# schematic.net
KiCad netlist of a schematic drawn in EAGLE
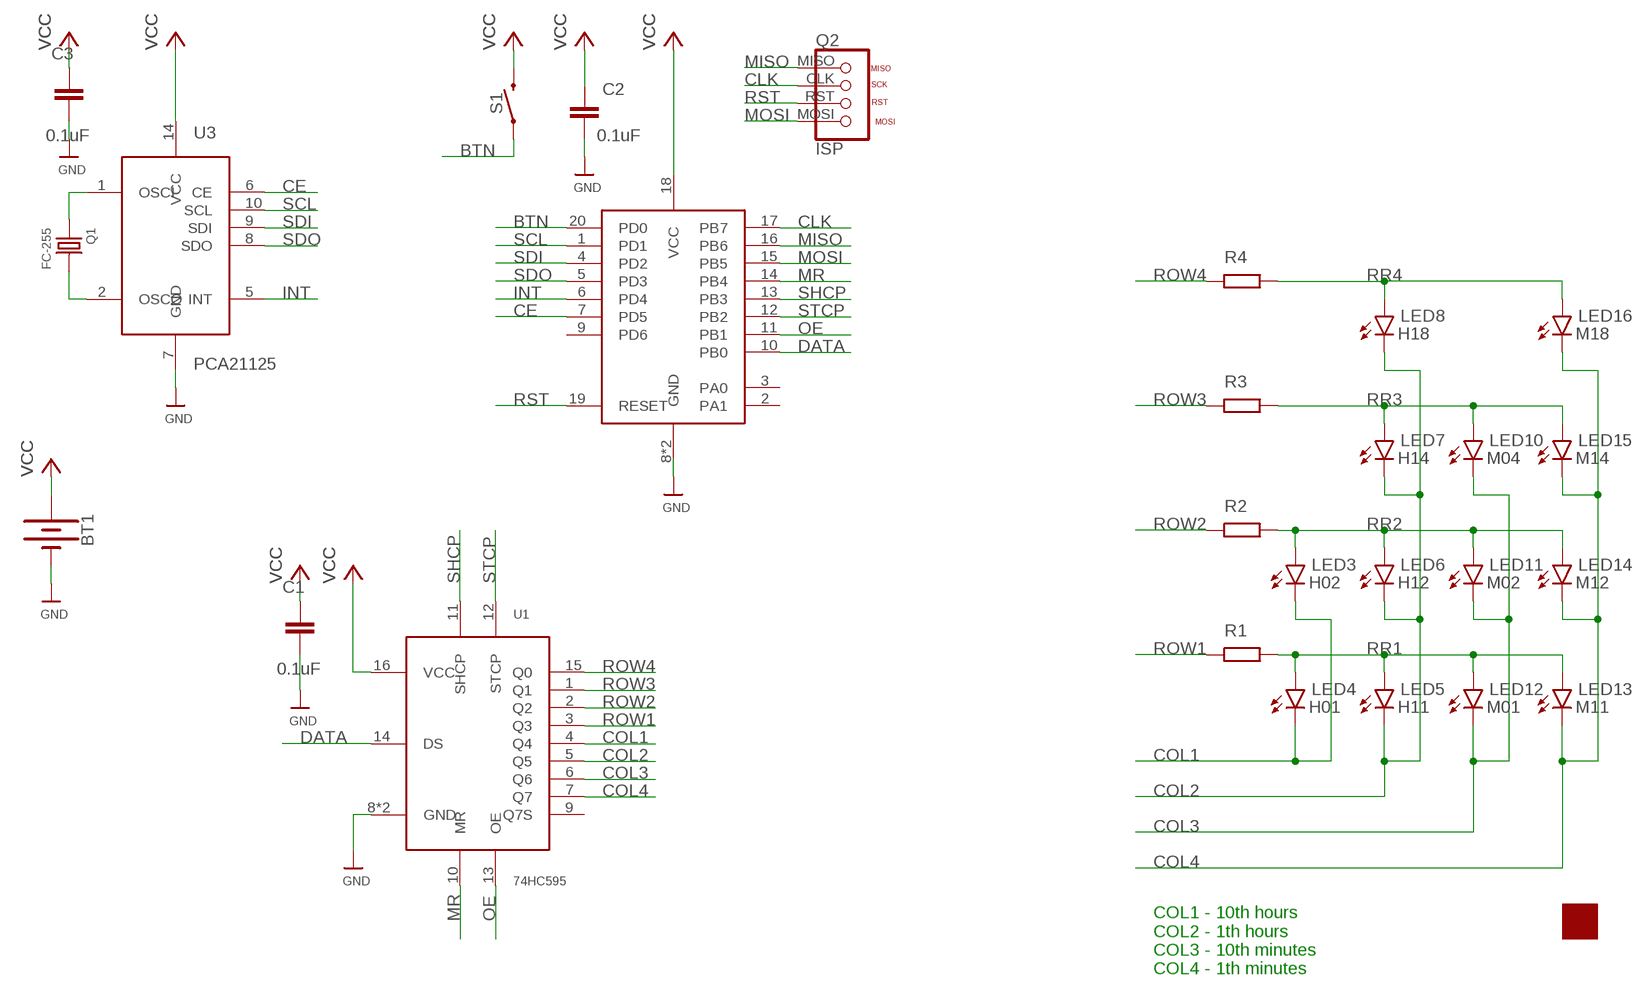
[diagram p0: schematic, sheet 1]

(export (version "E")
  (design (tool "Eeschema 10.0.6"))
  (components
    (comp (ref "BT1")
      (value "BATTERY-12MM_SMD")
      (footprint "eagle-import:BATTCON_12MM")
      (libsource (lib "eagle-import") (part "BATTERY-12MM_SMD"))
    )
    (comp (ref "C1")
      (value "0.1uF")
      (footprint "eagle-import:CAP_0402")
      (fields
        (field (name "DIGIKEY_PART_NUMBER") "311-2076-2-ND")
        (field (name "MANUFACTURER") "Yageo")
        (field (name "MPN") "CC0402CRNPO9BN1R0")
        (field (name "CREATED_BY") "PCBLayout.com")
      )
      (libsource (lib "eagle-import") (part "CC0402CRNPO9BN1R0"))
    )
    (comp (ref "C2")
      (value "0.1uF")
      (footprint "eagle-import:CAP_0402")
      (fields
        (field (name "DIGIKEY_PART_NUMBER") "311-2076-2-ND")
        (field (name "MANUFACTURER") "Yageo")
        (field (name "MPN") "CC0402CRNPO9BN1R0")
        (field (name "CREATED_BY") "PCBLayout.com")
      )
      (libsource (lib "eagle-import") (part "CC0402CRNPO9BN1R0"))
    )
    (comp (ref "C3")
      (value "0.1uF")
      (footprint "eagle-import:CAP_0402")
      (fields
        (field (name "DIGIKEY_PART_NUMBER") "311-2076-2-ND")
        (field (name "MANUFACTURER") "Yageo")
        (field (name "MPN") "CC0402CRNPO9BN1R0")
        (field (name "CREATED_BY") "PCBLayout.com")
      )
      (libsource (lib "eagle-import") (part "CC0402CRNPO9BN1R0"))
    )
    (comp (ref "IMG1")
      (value "IMAGE")
      (footprint "eagle-import:IMG6")
      (libsource (lib "eagle-import") (part "IMAGE"))
    )
    (comp (ref "LED3")
      (value "H02")
      (footprint "eagle-import:LG-T67K")
      (libsource (lib "eagle-import") (part "LG-T67K"))
    )
    (comp (ref "LED4")
      (value "H01")
      (footprint "eagle-import:LG-T67K")
      (libsource (lib "eagle-import") (part "LG-T67K"))
    )
    (comp (ref "LED5")
      (value "H11")
      (footprint "eagle-import:LG-T67K")
      (libsource (lib "eagle-import") (part "LG-T67K"))
    )
    (comp (ref "LED6")
      (value "H12")
      (footprint "eagle-import:LG-T67K")
      (libsource (lib "eagle-import") (part "LG-T67K"))
    )
    (comp (ref "LED7")
      (value "H14")
      (footprint "eagle-import:LG-T67K")
      (libsource (lib "eagle-import") (part "LG-T67K"))
    )
    (comp (ref "LED8")
      (value "H18")
      (footprint "eagle-import:LG-T67K")
      (libsource (lib "eagle-import") (part "LG-T67K"))
    )
    (comp (ref "LED10")
      (value "M04")
      (footprint "eagle-import:LG-T67K")
      (libsource (lib "eagle-import") (part "LG-T67K"))
    )
    (comp (ref "LED11")
      (value "M02")
      (footprint "eagle-import:LG-T67K")
      (libsource (lib "eagle-import") (part "LG-T67K"))
    )
    (comp (ref "LED12")
      (value "M01")
      (footprint "eagle-import:LG-T67K")
      (libsource (lib "eagle-import") (part "LG-T67K"))
    )
    (comp (ref "LED13")
      (value "M11")
      (footprint "eagle-import:LG-T67K")
      (libsource (lib "eagle-import") (part "LG-T67K"))
    )
    (comp (ref "LED14")
      (value "M12")
      (footprint "eagle-import:LG-T67K")
      (libsource (lib "eagle-import") (part "LG-T67K"))
    )
    (comp (ref "LED15")
      (value "M14")
      (footprint "eagle-import:LG-T67K")
      (libsource (lib "eagle-import") (part "LG-T67K"))
    )
    (comp (ref "LED16")
      (value "M18")
      (footprint "eagle-import:LG-T67K")
      (libsource (lib "eagle-import") (part "LG-T67K"))
    )
    (comp (ref "Q1")
      (value "FC-255")
      (footprint "eagle-import:FC-255")
      (libsource (lib "eagle-import") (part "FC-255"))
    )
    (comp (ref "Q2")
      (value "ISP")
      (footprint "eagle-import:ISP")
      (libsource (lib "eagle-import") (part "ISP"))
    )
    (comp (ref "R1")
      (value "R_CHIP-0402(1005-METRIC)")
      (footprint "eagle-import:RESC1005X40")
      (libsource (lib "eagle-import") (part "RCHIP-0402(1005-METRIC)_"))
    )
    (comp (ref "R2")
      (value "R_CHIP-0402(1005-METRIC)")
      (footprint "eagle-import:RESC1005X40")
      (libsource (lib "eagle-import") (part "RCHIP-0402(1005-METRIC)_"))
    )
    (comp (ref "R3")
      (value "R_CHIP-0402(1005-METRIC)")
      (footprint "eagle-import:RESC1005X40")
      (libsource (lib "eagle-import") (part "RCHIP-0402(1005-METRIC)_"))
    )
    (comp (ref "R4")
      (value "R_CHIP-0402(1005-METRIC)")
      (footprint "eagle-import:RESC1005X40")
      (libsource (lib "eagle-import") (part "RCHIP-0402(1005-METRIC)_"))
    )
    (comp (ref "S1")
      (value "MOMENTARY-SWITCH-SPST-SMD-6.2MM-TALL")
      (footprint "eagle-import:TACTILE_SWITCH_SMD_6.2MM_TALL")
      (libsource (lib "eagle-import") (part "MOMENTARY-SWITCH-SPST-SMD-6.2MM-TALL"))
    )
    (comp (ref "U1")
      (value "74HC595")
      (footprint "eagle-import:DHVQFN16")
      (libsource (lib "eagle-import") (part "74HC595"))
    )
    (comp (ref "U2")
      (value "ATTINY2313")
      (footprint "eagle-import:MLF20-4X4")
      (libsource (lib "eagle-import") (part "ATTINY2313AMLF20-4X4"))
    )
    (comp (ref "U3")
      (value "PCA21125")
      (footprint "eagle-import:TSSOP14")
      (libsource (lib "eagle-import") (part "PCA21125"))
    )
  )
  (nets
    (net (code "1") (name "/BTN") (class "Default")
      (node (ref "S1") (pin "A2") (pinfunction "1_A2") (pintype "passive"))
      (node (ref "U2") (pin "20") (pinfunction "PD0_20") (pintype "bidirectional"))
    )
    (net (code "2") (name "/CE") (class "Default")
      (node (ref "U2") (pin "7") (pinfunction "PD5_7") (pintype "bidirectional"))
      (node (ref "U3") (pin "6") (pinfunction "CE_6") (pintype "bidirectional"))
    )
    (net (code "3") (name "/CLK") (class "Default")
      (node (ref "Q2") (pin "CLK") (pinfunction "SCK_CLK") (pintype "passive"))
      (node (ref "U2") (pin "17") (pinfunction "PB7_17") (pintype "bidirectional"))
    )
    (net (code "4") (name "/COL1") (class "Default")
      (node (ref "LED3") (pin "P$2") (pinfunction "C_P$2") (pintype "passive"))
      (node (ref "LED4") (pin "P$2") (pinfunction "C_P$2") (pintype "passive"))
      (node (ref "U1") (pin "4") (pinfunction "Q4_4") (pintype "bidirectional"))
    )
    (net (code "5") (name "/COL2") (class "Default")
      (node (ref "LED5") (pin "P$2") (pinfunction "C_P$2") (pintype "passive"))
      (node (ref "LED6") (pin "P$2") (pinfunction "C_P$2") (pintype "passive"))
      (node (ref "LED7") (pin "P$2") (pinfunction "C_P$2") (pintype "passive"))
      (node (ref "LED8") (pin "P$2") (pinfunction "C_P$2") (pintype "passive"))
      (node (ref "U1") (pin "5") (pinfunction "Q5_5") (pintype "bidirectional"))
    )
    (net (code "6") (name "/COL3") (class "Default")
      (node (ref "LED10") (pin "P$2") (pinfunction "C_P$2") (pintype "passive"))
      (node (ref "LED11") (pin "P$2") (pinfunction "C_P$2") (pintype "passive"))
      (node (ref "LED12") (pin "P$2") (pinfunction "C_P$2") (pintype "passive"))
      (node (ref "U1") (pin "6") (pinfunction "Q6_6") (pintype "bidirectional"))
    )
    (net (code "7") (name "/COL4") (class "Default")
      (node (ref "LED13") (pin "P$2") (pinfunction "C_P$2") (pintype "passive"))
      (node (ref "LED14") (pin "P$2") (pinfunction "C_P$2") (pintype "passive"))
      (node (ref "LED15") (pin "P$2") (pinfunction "C_P$2") (pintype "passive"))
      (node (ref "LED16") (pin "P$2") (pinfunction "C_P$2") (pintype "passive"))
      (node (ref "U1") (pin "7") (pinfunction "Q7_7") (pintype "bidirectional"))
    )
    (net (code "8") (name "/DATA") (class "Default")
      (node (ref "U1") (pin "14") (pinfunction "DS_14") (pintype "bidirectional"))
      (node (ref "U2") (pin "10") (pinfunction "PB0_10") (pintype "bidirectional"))
    )
    (net (code "9") (name "/INT") (class "Default")
      (node (ref "U2") (pin "6") (pinfunction "PD4_6") (pintype "bidirectional"))
      (node (ref "U3") (pin "5") (pinfunction "INT_5") (pintype "bidirectional"))
    )
    (net (code "10") (name "/MISO") (class "Default")
      (node (ref "Q2") (pin "MISO") (pinfunction "MISO_MISO") (pintype "passive"))
      (node (ref "U2") (pin "16") (pinfunction "PB6_16") (pintype "bidirectional"))
    )
    (net (code "11") (name "/MOSI") (class "Default")
      (node (ref "Q2") (pin "MOSI") (pinfunction "MOSI_MOSI") (pintype "passive"))
      (node (ref "U2") (pin "15") (pinfunction "PB5_15") (pintype "bidirectional"))
    )
    (net (code "12") (name "/MR") (class "Default")
      (node (ref "U1") (pin "10") (pinfunction "MR_10") (pintype "bidirectional"))
      (node (ref "U2") (pin "14") (pinfunction "PB4_14") (pintype "bidirectional"))
    )
    (net (code "13") (name "/OE") (class "Default")
      (node (ref "U1") (pin "13") (pinfunction "OE_13") (pintype "bidirectional"))
      (node (ref "U2") (pin "11") (pinfunction "PB1_11") (pintype "bidirectional"))
    )
    (net (code "14") (name "/ROW1") (class "Default")
      (node (ref "R1") (pin "1") (pinfunction "1_1") (pintype "passive"))
      (node (ref "U1") (pin "3") (pinfunction "Q3_3") (pintype "bidirectional"))
    )
    (net (code "15") (name "/ROW2") (class "Default")
      (node (ref "R2") (pin "1") (pinfunction "1_1") (pintype "passive"))
      (node (ref "U1") (pin "2") (pinfunction "Q2_2") (pintype "bidirectional"))
    )
    (net (code "16") (name "/ROW3") (class "Default")
      (node (ref "R3") (pin "1") (pinfunction "1_1") (pintype "passive"))
      (node (ref "U1") (pin "1") (pinfunction "Q1_1") (pintype "bidirectional"))
    )
    (net (code "17") (name "/ROW4") (class "Default")
      (node (ref "R4") (pin "1") (pinfunction "1_1") (pintype "passive"))
      (node (ref "U1") (pin "15") (pinfunction "Q0_15") (pintype "bidirectional"))
    )
    (net (code "18") (name "/RR1") (class "Default")
      (node (ref "LED12") (pin "P$1") (pinfunction "A_P$1") (pintype "passive"))
      (node (ref "LED13") (pin "P$1") (pinfunction "A_P$1") (pintype "passive"))
      (node (ref "LED4") (pin "P$1") (pinfunction "A_P$1") (pintype "passive"))
      (node (ref "LED5") (pin "P$1") (pinfunction "A_P$1") (pintype "passive"))
      (node (ref "R1") (pin "2") (pinfunction "2_2") (pintype "passive"))
    )
    (net (code "19") (name "/RR2") (class "Default")
      (node (ref "LED11") (pin "P$1") (pinfunction "A_P$1") (pintype "passive"))
      (node (ref "LED14") (pin "P$1") (pinfunction "A_P$1") (pintype "passive"))
      (node (ref "LED3") (pin "P$1") (pinfunction "A_P$1") (pintype "passive"))
      (node (ref "LED6") (pin "P$1") (pinfunction "A_P$1") (pintype "passive"))
      (node (ref "R2") (pin "2") (pinfunction "2_2") (pintype "passive"))
    )
    (net (code "20") (name "/RR3") (class "Default")
      (node (ref "LED10") (pin "P$1") (pinfunction "A_P$1") (pintype "passive"))
      (node (ref "LED15") (pin "P$1") (pinfunction "A_P$1") (pintype "passive"))
      (node (ref "LED7") (pin "P$1") (pinfunction "A_P$1") (pintype "passive"))
      (node (ref "R3") (pin "2") (pinfunction "2_2") (pintype "passive"))
    )
    (net (code "21") (name "/RR4") (class "Default")
      (node (ref "LED16") (pin "P$1") (pinfunction "A_P$1") (pintype "passive"))
      (node (ref "LED8") (pin "P$1") (pinfunction "A_P$1") (pintype "passive"))
      (node (ref "R4") (pin "2") (pinfunction "2_2") (pintype "passive"))
    )
    (net (code "22") (name "/RST") (class "Default")
      (node (ref "Q2") (pin "RST") (pinfunction "RST_RST") (pintype "passive"))
      (node (ref "U2") (pin "19") (pinfunction "RESET_19") (pintype "bidirectional"))
    )
    (net (code "23") (name "/SCL") (class "Default")
      (node (ref "U2") (pin "1") (pinfunction "PD1_1") (pintype "bidirectional"))
      (node (ref "U3") (pin "10") (pinfunction "SCL_10") (pintype "bidirectional"))
    )
    (net (code "24") (name "/SDI") (class "Default")
      (node (ref "U2") (pin "4") (pinfunction "PD2_4") (pintype "bidirectional"))
      (node (ref "U3") (pin "9") (pinfunction "SDI_9") (pintype "bidirectional"))
    )
    (net (code "25") (name "/SDO") (class "Default")
      (node (ref "U2") (pin "5") (pinfunction "PD3_5") (pintype "bidirectional"))
      (node (ref "U3") (pin "8") (pinfunction "SDO_8") (pintype "bidirectional"))
    )
    (net (code "26") (name "/SHCP") (class "Default")
      (node (ref "U1") (pin "11") (pinfunction "SHCP_11") (pintype "bidirectional"))
      (node (ref "U2") (pin "13") (pinfunction "PB3_13") (pintype "bidirectional"))
    )
    (net (code "27") (name "/STCP") (class "Default")
      (node (ref "U1") (pin "12") (pinfunction "STCP_12") (pintype "bidirectional"))
      (node (ref "U2") (pin "12") (pinfunction "PB2_12") (pintype "bidirectional"))
    )
    (net (code "28") (name "GND") (class "Default")
      (node (ref "BT1") (pin "GND") (pinfunction "-_GND") (pintype "power_in"))
      (node (ref "C1") (pin "2") (pinfunction "2_2") (pintype "passive"))
      (node (ref "C2") (pin "2") (pinfunction "2_2") (pintype "passive"))
      (node (ref "C3") (pin "2") (pinfunction "2_2") (pintype "passive"))
      (node (ref "U1") (pin "8") (pinfunction "GND_8") (pintype "bidirectional"))
      (node (ref "U1") (pin "PAD") (pinfunction "GND_PAD") (pintype "bidirectional"))
      (node (ref "U2") (pin "8") (pinfunction "GND_8") (pintype "bidirectional"))
      (node (ref "U2") (pin "TH") (pinfunction "GND_TH") (pintype "bidirectional"))
      (node (ref "U3") (pin "7") (pinfunction "GND_7") (pintype "bidirectional"))
    )
    (net (code "29") (name "Net-(Q1-1)") (class "Default")
      (node (ref "Q1") (pin "IN") (pinfunction "1_IN") (pintype "passive"))
      (node (ref "U3") (pin "1") (pinfunction "OSCI_1") (pintype "bidirectional"))
    )
    (net (code "30") (name "Net-(Q1-2)") (class "Default")
      (node (ref "Q1") (pin "OUT") (pinfunction "2_OUT") (pintype "passive"))
      (node (ref "U3") (pin "2") (pinfunction "OSCO_2") (pintype "bidirectional"))
    )
    (net (code "31") (name "VCC") (class "Default")
      (node (ref "BT1") (pin "PWR@1") (pinfunction "+_PWR@1") (pintype "power_in"))
      (node (ref "C1") (pin "1") (pinfunction "1_1") (pintype "passive"))
      (node (ref "C2") (pin "1") (pinfunction "1_1") (pintype "passive"))
      (node (ref "C3") (pin "1") (pinfunction "1_1") (pintype "passive"))
      (node (ref "S1") (pin "B2") (pinfunction "2_B2") (pintype "passive"))
      (node (ref "U1") (pin "16") (pinfunction "VCC_16") (pintype "bidirectional"))
      (node (ref "U2") (pin "18") (pinfunction "VCC_18") (pintype "bidirectional"))
      (node (ref "U3") (pin "14") (pinfunction "VCC_14") (pintype "bidirectional"))
    )
    (net (code "32") (name "unconnected-(U1-Q7S-Pad9)") (class "Default")
      (node (ref "U1") (pin "9") (pinfunction "Q7S_9") (pintype "bidirectional"))
    )
    (net (code "33") (name "unconnected-(U2-PA0-Pad3)") (class "Default")
      (node (ref "U2") (pin "3") (pinfunction "PA0_3") (pintype "bidirectional"))
    )
    (net (code "34") (name "unconnected-(U2-PA1-Pad2)") (class "Default")
      (node (ref "U2") (pin "2") (pinfunction "PA1_2") (pintype "bidirectional"))
    )
    (net (code "35") (name "unconnected-(U2-PD6-Pad9)") (class "Default")
      (node (ref "U2") (pin "9") (pinfunction "PD6_9") (pintype "bidirectional"))
    )
  )
)
